# mcu.net
KiCad netlist of a schematic drawn in Altium Designer
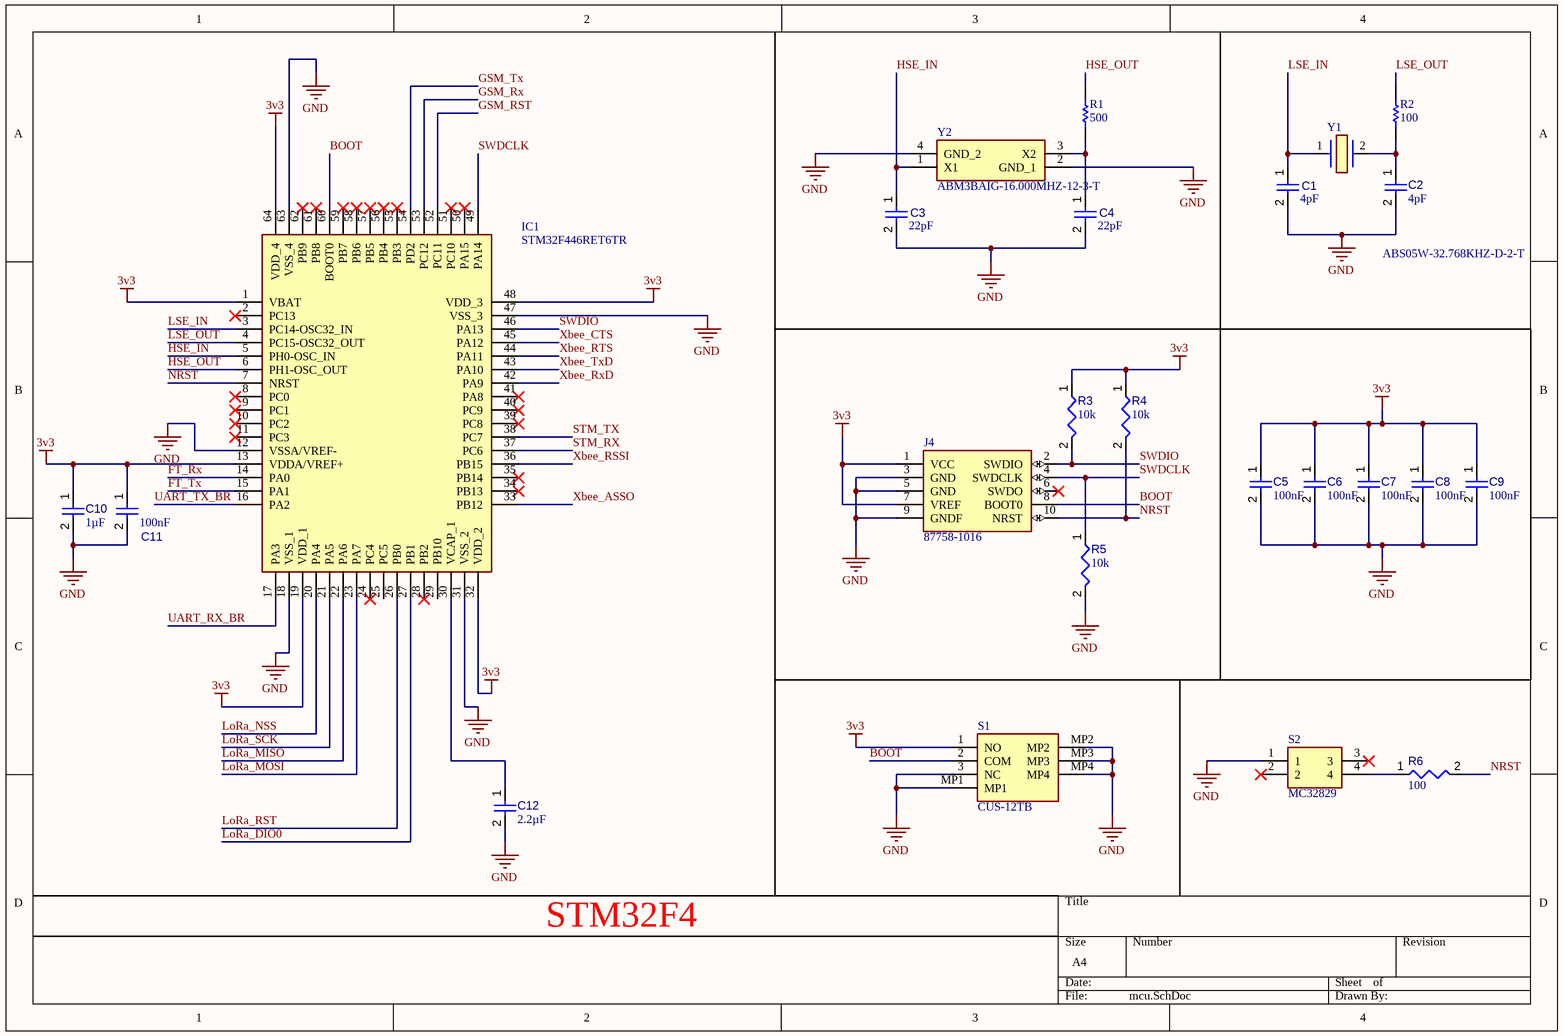
[diagram p0:  mcu.SchDoc]

(export (version "E")
  (design (tool "Eeschema 10.0.6"))
  (components
    (comp (ref "C1")
      (value "4pF")
      (footprint "CAPC1608X90X40LL10T20")
      (description "Chip Capacitor, 1 uF, +/- 10%, 25 V, 0603 (1608 Metric)")
      (fields (field (name "TOLERANCE") "10%") (field (name "Comment") "Capacitor 1 uF +/- 10% 25 V 0603"))
      (libsource (lib "Shlok Sharma") (part "CAP-NP-2"))
    )
    (comp (ref "C2")
      (value "4pF")
      (footprint "CAPC1608X90X40LL10T20")
      (description "Chip Capacitor, 1 uF, +/- 10%, 25 V, 0603 (1608 Metric)")
      (fields (field (name "TOLERANCE") "10%") (field (name "Comment") "Capacitor 1 uF +/- 10% 25 V 0603"))
      (libsource (lib "Shlok Sharma") (part "CAP-NP-2"))
    )
    (comp (ref "C3")
      (value "22pF")
      (footprint "CAPC1608X90X40LL10T20")
      (description "Chip Capacitor, 1 uF, +/- 10%, 25 V, 0603 (1608 Metric)")
      (fields (field (name "TOLERANCE") "10%") (field (name "Comment") "Capacitor 1 uF +/- 10% 25 V 0603"))
      (libsource (lib "Shlok Sharma") (part "CAP-NP-2"))
    )
    (comp (ref "C4")
      (value "22pF")
      (footprint "CAPC1608X90X40LL10T20")
      (description "Chip Capacitor, 1 uF, +/- 10%, 25 V, 0603 (1608 Metric)")
      (fields (field (name "TOLERANCE") "10%") (field (name "Comment") "Capacitor 1 uF +/- 10% 25 V 0603"))
      (libsource (lib "Shlok Sharma") (part "CAP-NP-2"))
    )
    (comp (ref "C5")
      (value "100nF")
      (footprint "CAPC1608X90X40NL10T20")
      (description "Chip Capacitor, 100 nF, +/- 10%, 50 V, 0603 (1608 Metric)")
      (fields (field (name "TOLERANCE") "10%") (field (name "Comment") "Capacitor 100 nF +/-10% 50 V 0603"))
      (libsource (lib "Shlok Sharma") (part "CAP-NP-2"))
    )
    (comp (ref "C6")
      (value "100nF")
      (footprint "CAPC1608X90X40NL10T20")
      (description "Chip Capacitor, 100 nF, +/- 10%, 50 V, 0603 (1608 Metric)")
      (fields (field (name "TOLERANCE") "10%") (field (name "Comment") "Capacitor 100 nF +/-10% 50 V 0603"))
      (libsource (lib "Shlok Sharma") (part "CAP-NP-2"))
    )
    (comp (ref "C7")
      (value "100nF")
      (footprint "CAPC1608X90X40NL10T20")
      (description "Chip Capacitor, 100 nF, +/- 10%, 50 V, 0603 (1608 Metric)")
      (fields (field (name "TOLERANCE") "10%") (field (name "Comment") "Capacitor 100 nF +/-10% 50 V 0603"))
      (libsource (lib "Shlok Sharma") (part "CAP-NP-2"))
    )
    (comp (ref "C8")
      (value "100nF")
      (footprint "CAPC1608X90X40NL10T20")
      (description "Chip Capacitor, 100 nF, +/- 10%, 50 V, 0603 (1608 Metric)")
      (fields (field (name "TOLERANCE") "10%") (field (name "Comment") "Capacitor 100 nF +/-10% 50 V 0603"))
      (libsource (lib "Shlok Sharma") (part "CAP-NP-2"))
    )
    (comp (ref "C9")
      (value "100nF")
      (footprint "CAPC1608X90X40NL10T20")
      (description "Chip Capacitor, 100 nF, +/- 10%, 50 V, 0603 (1608 Metric)")
      (fields (field (name "TOLERANCE") "10%") (field (name "Comment") "Capacitor 100 nF +/-10% 50 V 0603"))
      (libsource (lib "Shlok Sharma") (part "CAP-NP-2"))
    )
    (comp (ref "C10")
      (value "1µF")
      (footprint "CAPC2013X135X45NL10T25")
      (description "Chip Capacitor, 1 uF, +/- 10%, 50 V, 0805 (2012 Metric)")
      (fields (field (name "TOLERANCE") "10%") (field (name "Comment") "Capacitor 1 uF +/- 10% 50 V 0805"))
      (libsource (lib "Shlok Sharma") (part "CAP-NP-2"))
    )
    (comp (ref "C11")
      (value "100nF")
      (footprint "CAPC1608X90X40NL10T20")
      (description "Chip Capacitor, 100 nF, +/- 10%, 50 V, 0603 (1608 Metric)")
      (fields (field (name "TOLERANCE") "10%") (field (name "Comment") "Capacitor 100 nF +/-10% 50 V 0603"))
      (libsource (lib "Shlok Sharma") (part "CAP-NP-2"))
    )
    (comp (ref "C12")
      (value "2.2µF")
      (footprint "CAPC2013X135X45NL10T25")
      (description "Chip Capacitor, 1 uF, +/- 10%, 50 V, 0805 (2012 Metric)")
      (fields (field (name "TOLERANCE") "10%") (field (name "Comment") "Capacitor 1 uF +/- 10% 50 V 0805"))
      (libsource (lib "Shlok Sharma") (part "CAP-NP-2"))
    )
    (comp (ref "IC1")
      (value "STM32F446RET6TR")
      (footprint "SamacSys:QFP50P1200X1200X160-64N")
      (description "Integrated Circuit")
      (fields (field (name "MOUSER PART NUMBER") "511-STM32F446RET6TR"))
      (libsource (lib "*") (part "STM32F446RET6TR"))
    )
    (comp (ref "J4")
      (value "87758-1016")
      (footprint "SamacSys:HDRV10W75P200_2X5_990X400X595P")
      (description "Connector")
      (fields (field (name "MOUSER PART NUMBER") "538-87758-1016"))
      (libsource (lib "SamacSys") (part "87758-1016"))
    )
    (comp (ref "R1")
      (value "500")
      (footprint "RESC1005X40X25ML05T05")
      (description "Chip Resistor, 0 Ohm, 0.1 W, -55 to 155 degC, 0402 (1005 Metric)")
      (fields (field (name "TOLERANCE") "5%") (field (name "POWER") "100mW"))
      (libsource (lib "") (part "RES-2_1"))
    )
    (comp (ref "R2")
      (value "100")
      (footprint "RESC1005X40X25ML05T05")
      (description "Chip Resistor, 0 Ohm, 0.1 W, -55 to 155 degC, 0402 (1005 Metric)")
      (fields (field (name "TOLERANCE") "5%") (field (name "POWER") "100mW"))
      (libsource (lib "") (part "RES-2_1"))
    )
    (comp (ref "R3")
      (value "10k")
      (footprint "RESC1608X55X25ML10T15")
      (description "Chip Resistor, 10 KOhm, +/- 1%, 01 W, -55 to 155 degC, 0603 (1608 Metric)")
      (fields (field (name "POWER") "100mW") (field (name "TOLERANCE") "1%"))
      (libsource (lib "Shlok Sharma") (part "RES-2"))
    )
    (comp (ref "R4")
      (value "10k")
      (footprint "RESC1608X55X25ML10T15")
      (description "Chip Resistor, 10 KOhm, +/- 1%, 01 W, -55 to 155 degC, 0603 (1608 Metric)")
      (fields (field (name "POWER") "100mW") (field (name "TOLERANCE") "1%"))
      (libsource (lib "Shlok Sharma") (part "RES-2"))
    )
    (comp (ref "R5")
      (value "10k")
      (footprint "RESC1608X55X25ML10T15")
      (description "Chip Resistor, 10 KOhm, +/- 1%, 01 W, -55 to 155 degC, 0603 (1608 Metric)")
      (fields (field (name "POWER") "100mW") (field (name "TOLERANCE") "1%"))
      (libsource (lib "Shlok Sharma") (part "RES-2"))
    )
    (comp (ref "R6")
      (value "100")
      (footprint "RESC1608X55X25ML10T15")
      (description "Chip Resistor, 10 KOhm, +/- 1%, 01 W, -55 to 155 degC, 0603 (1608 Metric)")
      (fields (field (name "POWER") "100mW") (field (name "TOLERANCE") "1%"))
      (libsource (lib "Shlok Sharma") (part "RES-2"))
    )
    (comp (ref "S1")
      (value "CUS-12TB")
      (footprint "SamacSys:CUS12TB")
      (description "Switch")
      (fields (field (name "MOUSER PART NUMBER") "229-CUS-12TB"))
      (libsource (lib "SamacSys") (part "CUS-12TB"))
    )
    (comp (ref "S2")
      (value "MC32829")
      (footprint "SamacSys:MC32829")
      (description "Switch")
      (libsource (lib "*") (part "MC32829"))
    )
    (comp (ref "Y1")
      (value "ABS05W-32.768KHZ-D-2-T")
      (footprint "SamacSys:ABS05W32768KHZD2T")
      (description "Crystal or Oscillator")
      (fields (field (name "MOUSER PART NUMBER") "815-ABS05W32.768KD2T"))
      (libsource (lib "*") (part "ABS05W-32.768KHZ-D-2-T"))
    )
    (comp (ref "Y2")
      (value "ABM3BAIG-16.000MHZ-12-3-T")
      (footprint "SamacSys:ABM3BAIG")
      (description "Crystal or Oscillator")
      (libsource (lib "*") (part "ABM3BAIG-16.000MHZ-12-3-T"))
    )
  )
  (nets
    (net (code "1") (name "/BOOT") (class "Default")
      (node (ref "IC1") (pin "60") (pinfunction "BOOT0_60") (pintype "passive"))
      (node (ref "J4") (pin "8") (pinfunction "BOOT0_8") (pintype "passive"))
      (node (ref "S1") (pin "2") (pinfunction "COM_2") (pintype "passive"))
    )
    (net (code "2") (name "/FT_Rx") (class "Default")
      (node (ref "IC1") (pin "14") (pinfunction "PA0_14") (pintype "passive"))
    )
    (net (code "3") (name "/FT_Tx") (class "Default")
      (node (ref "IC1") (pin "15") (pinfunction "PA1_15") (pintype "passive"))
    )
    (net (code "4") (name "/GSM_RST") (class "Default")
      (node (ref "IC1") (pin "52") (pinfunction "PC11_52") (pintype "passive"))
    )
    (net (code "5") (name "/GSM_Rx") (class "Default")
      (node (ref "IC1") (pin "53") (pinfunction "PC12_53") (pintype "passive"))
    )
    (net (code "6") (name "/GSM_Tx") (class "Default")
      (node (ref "IC1") (pin "54") (pinfunction "PD2_54") (pintype "passive"))
    )
    (net (code "7") (name "/HSE_IN") (class "Default")
      (node (ref "C3") (pin "1") (pinfunction "1_1") (pintype "passive"))
      (node (ref "IC1") (pin "5") (pinfunction "PH0-OSC_IN_5") (pintype "passive"))
      (node (ref "Y2") (pin "1") (pinfunction "X1_1") (pintype "passive"))
    )
    (net (code "8") (name "/HSE_OUT") (class "Default")
      (node (ref "IC1") (pin "6") (pinfunction "PH1-OSC_OUT_6") (pintype "passive"))
      (node (ref "R1") (pin "2") (pinfunction "2_2") (pintype "passive"))
    )
    (net (code "9") (name "/LSE_IN") (class "Default")
      (node (ref "C1") (pin "1") (pinfunction "1_1") (pintype "passive"))
      (node (ref "IC1") (pin "3") (pinfunction "PC14-OSC32_IN_3") (pintype "passive"))
      (node (ref "Y1") (pin "1") (pinfunction "1_1") (pintype "passive"))
    )
    (net (code "10") (name "/LSE_OUT") (class "Default")
      (node (ref "IC1") (pin "4") (pinfunction "PC15-OSC32_OUT_4") (pintype "passive"))
      (node (ref "R2") (pin "2") (pinfunction "2_2") (pintype "passive"))
    )
    (net (code "11") (name "/LoRa_DIO0") (class "Default")
      (node (ref "IC1") (pin "27") (pinfunction "PB1_27") (pintype "passive"))
    )
    (net (code "12") (name "/LoRa_MISO") (class "Default")
      (node (ref "IC1") (pin "22") (pinfunction "PA6_22") (pintype "passive"))
    )
    (net (code "13") (name "/LoRa_MOSI") (class "Default")
      (node (ref "IC1") (pin "23") (pinfunction "PA7_23") (pintype "passive"))
    )
    (net (code "14") (name "/LoRa_NSS") (class "Default")
      (node (ref "IC1") (pin "20") (pinfunction "PA4_20") (pintype "passive"))
    )
    (net (code "15") (name "/LoRa_RST") (class "Default")
      (node (ref "IC1") (pin "26") (pinfunction "PB0_26") (pintype "passive"))
    )
    (net (code "16") (name "/LoRa_SCK") (class "Default")
      (node (ref "IC1") (pin "21") (pinfunction "PA5_21") (pintype "passive"))
    )
    (net (code "17") (name "/NRST") (class "Default")
      (node (ref "IC1") (pin "7") (pinfunction "NRST_7") (pintype "passive"))
      (node (ref "J4") (pin "10") (pinfunction "NRST_10") (pintype "bidirectional"))
      (node (ref "R4") (pin "2") (pinfunction "2_2") (pintype "passive"))
      (node (ref "R6") (pin "2") (pinfunction "2_2") (pintype "passive"))
    )
    (net (code "18") (name "/STM_RX") (class "Default")
      (node (ref "IC1") (pin "37") (pinfunction "PC6_37") (pintype "passive"))
    )
    (net (code "19") (name "/STM_TX") (class "Default")
      (node (ref "IC1") (pin "38") (pinfunction "PC7_38") (pintype "passive"))
    )
    (net (code "20") (name "/SWDCLK") (class "Default")
      (node (ref "IC1") (pin "49") (pinfunction "PA14_49") (pintype "passive"))
      (node (ref "J4") (pin "4") (pinfunction "SWDCLK_4") (pintype "bidirectional"))
      (node (ref "R5") (pin "1") (pinfunction "1_1") (pintype "passive"))
    )
    (net (code "21") (name "/SWDIO") (class "Default")
      (node (ref "IC1") (pin "46") (pinfunction "PA13_46") (pintype "passive"))
      (node (ref "J4") (pin "2") (pinfunction "SWDIO_2") (pintype "bidirectional"))
      (node (ref "R3") (pin "2") (pinfunction "2_2") (pintype "passive"))
    )
    (net (code "22") (name "/UART_RX_BR") (class "Default")
      (node (ref "IC1") (pin "17") (pinfunction "PA3_17") (pintype "passive"))
    )
    (net (code "23") (name "/UART_TX_BR") (class "Default")
      (node (ref "IC1") (pin "16") (pinfunction "PA2_16") (pintype "passive"))
    )
    (net (code "24") (name "/Xbee_ASSO") (class "Default")
      (node (ref "IC1") (pin "33") (pinfunction "PB12_33") (pintype "passive"))
    )
    (net (code "25") (name "/Xbee_CTS") (class "Default")
      (node (ref "IC1") (pin "45") (pinfunction "PA12_45") (pintype "passive"))
    )
    (net (code "26") (name "/Xbee_RSSI") (class "Default")
      (node (ref "IC1") (pin "36") (pinfunction "PB15_36") (pintype "passive"))
    )
    (net (code "27") (name "/Xbee_RTS") (class "Default")
      (node (ref "IC1") (pin "44") (pinfunction "PA11_44") (pintype "passive"))
    )
    (net (code "28") (name "/Xbee_RxD") (class "Default")
      (node (ref "IC1") (pin "42") (pinfunction "PA9_42") (pintype "passive"))
    )
    (net (code "29") (name "/Xbee_TxD") (class "Default")
      (node (ref "IC1") (pin "43") (pinfunction "PA10_43") (pintype "passive"))
    )
    (net (code "30") (name "3v3") (class "Default")
      (node (ref "C10") (pin "1") (pinfunction "1_1") (pintype "passive"))
      (node (ref "C11") (pin "1") (pinfunction "1_1") (pintype "passive"))
      (node (ref "C5") (pin "1") (pinfunction "1_1") (pintype "passive"))
      (node (ref "C6") (pin "1") (pinfunction "1_1") (pintype "passive"))
      (node (ref "C7") (pin "1") (pinfunction "1_1") (pintype "passive"))
      (node (ref "C8") (pin "1") (pinfunction "1_1") (pintype "passive"))
      (node (ref "C9") (pin "1") (pinfunction "1_1") (pintype "passive"))
      (node (ref "IC1") (pin "1") (pinfunction "VBAT_1") (pintype "passive"))
      (node (ref "IC1") (pin "13") (pinfunction "VDDA/VREF+_13") (pintype "passive"))
      (node (ref "IC1") (pin "19") (pinfunction "VDD_1_19") (pintype "passive"))
      (node (ref "IC1") (pin "32") (pinfunction "VDD_2_32") (pintype "passive"))
      (node (ref "IC1") (pin "48") (pinfunction "VDD_3_48") (pintype "passive"))
      (node (ref "IC1") (pin "64") (pinfunction "VDD_4_64") (pintype "passive"))
      (node (ref "J4") (pin "1") (pinfunction "VCC_1") (pintype "passive"))
      (node (ref "J4") (pin "7") (pinfunction "VREF_7") (pintype "passive"))
      (node (ref "R3") (pin "1") (pinfunction "1_1") (pintype "passive"))
      (node (ref "R4") (pin "1") (pinfunction "1_1") (pintype "passive"))
      (node (ref "S1") (pin "1") (pinfunction "NO_1") (pintype "passive"))
    )
    (net (code "31") (name "GND") (class "Default")
      (node (ref "C1") (pin "2") (pinfunction "2_2") (pintype "passive"))
      (node (ref "C10") (pin "2") (pinfunction "2_2") (pintype "passive"))
      (node (ref "C11") (pin "2") (pinfunction "2_2") (pintype "passive"))
      (node (ref "C12") (pin "2") (pinfunction "2_2") (pintype "passive"))
      (node (ref "C2") (pin "2") (pinfunction "2_2") (pintype "passive"))
      (node (ref "C3") (pin "2") (pinfunction "2_2") (pintype "passive"))
      (node (ref "C4") (pin "2") (pinfunction "2_2") (pintype "passive"))
      (node (ref "C5") (pin "2") (pinfunction "2_2") (pintype "passive"))
      (node (ref "C6") (pin "2") (pinfunction "2_2") (pintype "passive"))
      (node (ref "C7") (pin "2") (pinfunction "2_2") (pintype "passive"))
      (node (ref "C8") (pin "2") (pinfunction "2_2") (pintype "passive"))
      (node (ref "C9") (pin "2") (pinfunction "2_2") (pintype "passive"))
      (node (ref "IC1") (pin "12") (pinfunction "VSSA/VREF-_12") (pintype "passive"))
      (node (ref "IC1") (pin "18") (pinfunction "VSS_1_18") (pintype "passive"))
      (node (ref "IC1") (pin "31") (pinfunction "VSS_2_31") (pintype "passive"))
      (node (ref "IC1") (pin "47") (pinfunction "VSS_3_47") (pintype "passive"))
      (node (ref "IC1") (pin "63") (pinfunction "VSS_4_63") (pintype "passive"))
      (node (ref "J4") (pin "3") (pinfunction "GND_3") (pintype "passive"))
      (node (ref "J4") (pin "5") (pinfunction "GND_5") (pintype "passive"))
      (node (ref "J4") (pin "9") (pinfunction "GNDF_9") (pintype "passive"))
      (node (ref "R5") (pin "2") (pinfunction "2_2") (pintype "passive"))
      (node (ref "S1") (pin "3") (pinfunction "NC_3") (pintype "passive"))
      (node (ref "S1") (pin "MP1") (pinfunction "MP1_MP1") (pintype "passive"))
      (node (ref "S1") (pin "MP2") (pinfunction "MP2_MP2") (pintype "passive"))
      (node (ref "S1") (pin "MP3") (pinfunction "MP3_MP3") (pintype "passive"))
      (node (ref "S1") (pin "MP4") (pinfunction "MP4_MP4") (pintype "passive"))
      (node (ref "S2") (pin "1") (pinfunction "1_1") (pintype "passive"))
      (node (ref "Y2") (pin "2") (pinfunction "GND_1_2") (pintype "passive"))
      (node (ref "Y2") (pin "4") (pinfunction "GND_2_4") (pintype "passive"))
    )
    (net (code "32") (name "Net-(C2-Pad1)") (class "Default")
      (node (ref "C2") (pin "1") (pinfunction "1_1") (pintype "passive"))
      (node (ref "R2") (pin "1") (pinfunction "1_1") (pintype "passive"))
      (node (ref "Y1") (pin "2") (pinfunction "2_2") (pintype "passive"))
    )
    (net (code "33") (name "Net-(IC1-VCAP_1)") (class "Default")
      (node (ref "C12") (pin "1") (pinfunction "1_1") (pintype "passive"))
      (node (ref "IC1") (pin "30") (pinfunction "VCAP_1_30") (pintype "passive"))
    )
    (net (code "34") (name "Net-(R6-Pad1)") (class "Default")
      (node (ref "R6") (pin "1") (pinfunction "1_1") (pintype "passive"))
      (node (ref "S2") (pin "4") (pinfunction "4_4") (pintype "passive"))
    )
    (net (code "35") (name "Net-(Y2-X2)") (class "Default")
      (node (ref "C4") (pin "1") (pinfunction "1_1") (pintype "passive"))
      (node (ref "R1") (pin "1") (pinfunction "1_1") (pintype "passive"))
      (node (ref "Y2") (pin "3") (pinfunction "X2_3") (pintype "passive"))
    )
    (net (code "36") (name "unconnected-(IC1-PA8-Pad41)") (class "Default")
      (node (ref "IC1") (pin "41") (pinfunction "PA8_41") (pintype "passive+no_connect"))
    )
    (net (code "37") (name "unconnected-(IC1-PA15-Pad50)") (class "Default")
      (node (ref "IC1") (pin "50") (pinfunction "PA15_50") (pintype "passive+no_connect"))
    )
    (net (code "38") (name "unconnected-(IC1-PB2-Pad28)") (class "Default")
      (node (ref "IC1") (pin "28") (pinfunction "PB2_28") (pintype "passive+no_connect"))
    )
    (net (code "39") (name "unconnected-(IC1-PB3-Pad55)") (class "Default")
      (node (ref "IC1") (pin "55") (pinfunction "PB3_55") (pintype "passive+no_connect"))
    )
    (net (code "40") (name "unconnected-(IC1-PB4-Pad56)") (class "Default")
      (node (ref "IC1") (pin "56") (pinfunction "PB4_56") (pintype "passive+no_connect"))
    )
    (net (code "41") (name "unconnected-(IC1-PB5-Pad57)") (class "Default")
      (node (ref "IC1") (pin "57") (pinfunction "PB5_57") (pintype "passive+no_connect"))
    )
    (net (code "42") (name "unconnected-(IC1-PB6-Pad58)") (class "Default")
      (node (ref "IC1") (pin "58") (pinfunction "PB6_58") (pintype "passive+no_connect"))
    )
    (net (code "43") (name "unconnected-(IC1-PB7-Pad59)") (class "Default")
      (node (ref "IC1") (pin "59") (pinfunction "PB7_59") (pintype "passive+no_connect"))
    )
    (net (code "44") (name "unconnected-(IC1-PB8-Pad61)") (class "Default")
      (node (ref "IC1") (pin "61") (pinfunction "PB8_61") (pintype "passive+no_connect"))
    )
    (net (code "45") (name "unconnected-(IC1-PB9-Pad62)") (class "Default")
      (node (ref "IC1") (pin "62") (pinfunction "PB9_62") (pintype "passive+no_connect"))
    )
    (net (code "46") (name "unconnected-(IC1-PB10-Pad29)") (class "Default")
      (node (ref "IC1") (pin "29") (pinfunction "PB10_29") (pintype "passive"))
    )
    (net (code "47") (name "unconnected-(IC1-PB13-Pad34)") (class "Default")
      (node (ref "IC1") (pin "34") (pinfunction "PB13_34") (pintype "passive+no_connect"))
    )
    (net (code "48") (name "unconnected-(IC1-PB14-Pad35)") (class "Default")
      (node (ref "IC1") (pin "35") (pinfunction "PB14_35") (pintype "passive+no_connect"))
    )
    (net (code "49") (name "unconnected-(IC1-PC0-Pad8)") (class "Default")
      (node (ref "IC1") (pin "8") (pinfunction "PC0_8") (pintype "passive+no_connect"))
    )
    (net (code "50") (name "unconnected-(IC1-PC1-Pad9)") (class "Default")
      (node (ref "IC1") (pin "9") (pinfunction "PC1_9") (pintype "passive+no_connect"))
    )
    (net (code "51") (name "unconnected-(IC1-PC2-Pad10)") (class "Default")
      (node (ref "IC1") (pin "10") (pinfunction "PC2_10") (pintype "passive+no_connect"))
    )
    (net (code "52") (name "unconnected-(IC1-PC3-Pad11)") (class "Default")
      (node (ref "IC1") (pin "11") (pinfunction "PC3_11") (pintype "passive+no_connect"))
    )
    (net (code "53") (name "unconnected-(IC1-PC4-Pad24)") (class "Default")
      (node (ref "IC1") (pin "24") (pinfunction "PC4_24") (pintype "passive+no_connect"))
    )
    (net (code "54") (name "unconnected-(IC1-PC5-Pad25)") (class "Default")
      (node (ref "IC1") (pin "25") (pinfunction "PC5_25") (pintype "passive"))
    )
    (net (code "55") (name "unconnected-(IC1-PC8-Pad39)") (class "Default")
      (node (ref "IC1") (pin "39") (pinfunction "PC8_39") (pintype "passive+no_connect"))
    )
    (net (code "56") (name "unconnected-(IC1-PC9-Pad40)") (class "Default")
      (node (ref "IC1") (pin "40") (pinfunction "PC9_40") (pintype "passive+no_connect"))
    )
    (net (code "57") (name "unconnected-(IC1-PC10-Pad51)") (class "Default")
      (node (ref "IC1") (pin "51") (pinfunction "PC10_51") (pintype "passive+no_connect"))
    )
    (net (code "58") (name "unconnected-(IC1-PC13-Pad2)") (class "Default")
      (node (ref "IC1") (pin "2") (pinfunction "PC13_2") (pintype "passive+no_connect"))
    )
    (net (code "59") (name "unconnected-(J4-SWDO-Pad6)") (class "Default")
      (node (ref "J4") (pin "6") (pinfunction "SWDO_6") (pintype "bidirectional+no_connect"))
    )
    (net (code "60") (name "unconnected-(S2-Pad2)") (class "Default")
      (node (ref "S2") (pin "2") (pinfunction "2_2") (pintype "passive+no_connect"))
    )
    (net (code "61") (name "unconnected-(S2-Pad3)") (class "Default")
      (node (ref "S2") (pin "3") (pinfunction "3_3") (pintype "passive+no_connect"))
    )
  )
)
